# FPGA.net
KiCad netlist of a schematic drawn in Altium Designer
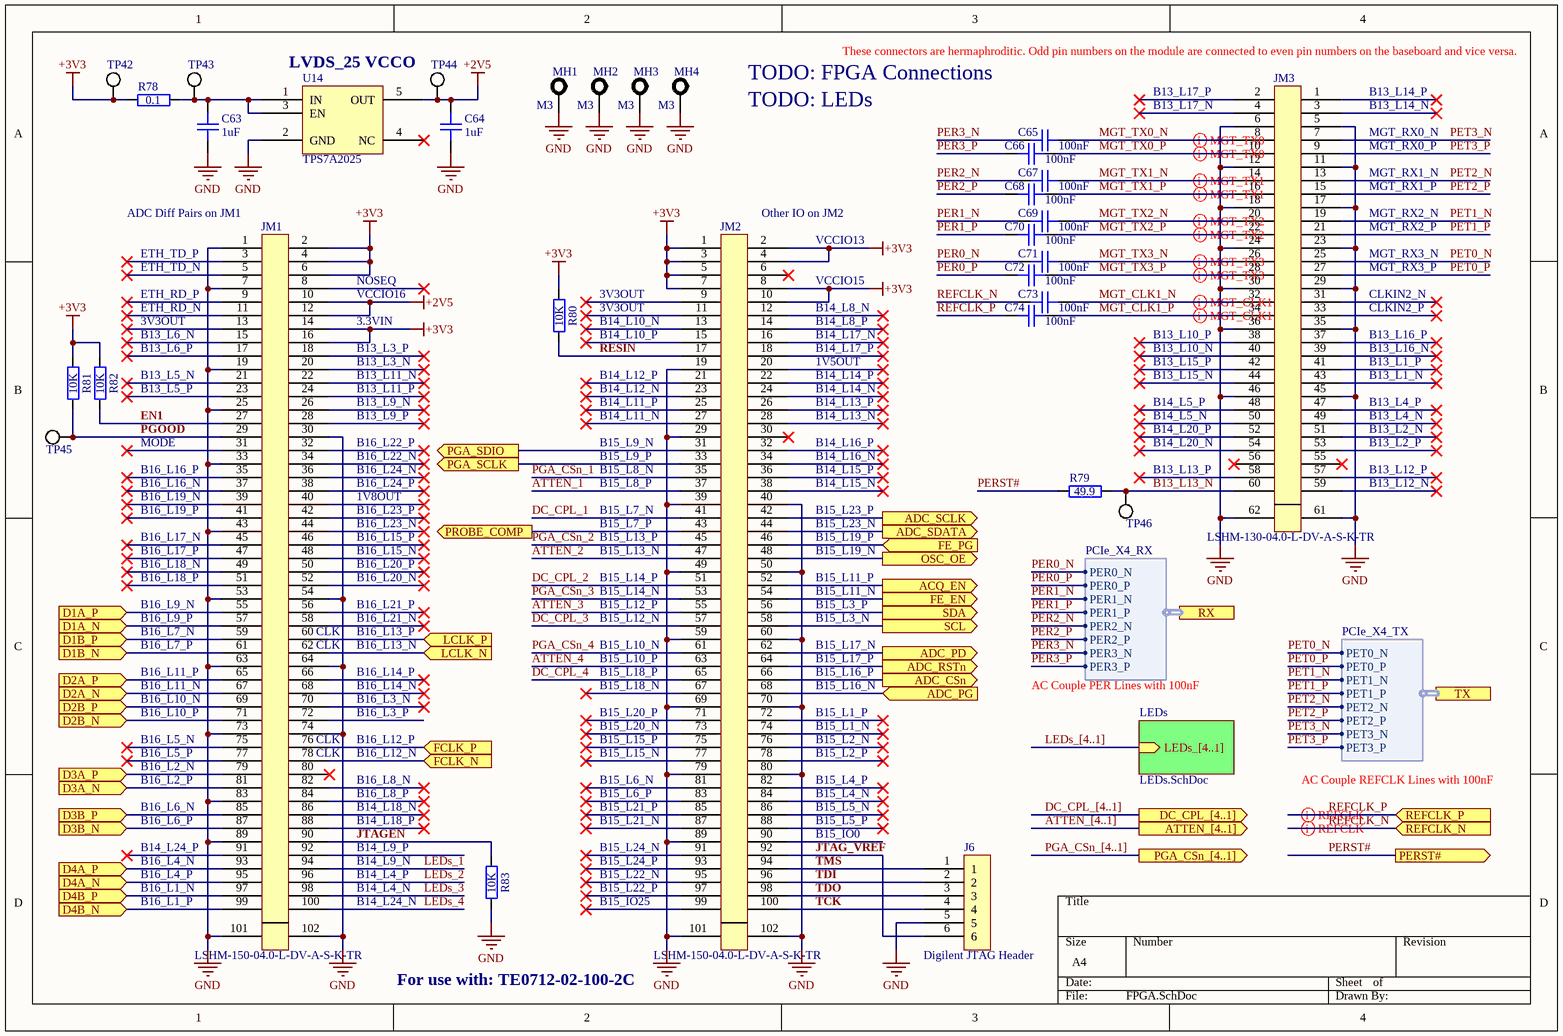
[diagram p0: FPGA.SchDoc]

(export (version "E")
  (design (tool "Eeschema 10.0.6"))
  (components
    (comp (ref "C63")
      (value "1uF")
      (footprint "GEN_C_0402")
      (libsource (lib "DSO") (part "CAP 1uF 25V X5R 0402"))
    )
    (comp (ref "C64")
      (value "1uF")
      (footprint "GEN_C_0402")
      (libsource (lib "DSO") (part "CAP 1uF 25V X5R 0402"))
    )
    (comp (ref "C65")
      (value "100nF")
      (footprint "GEN_C_0402")
      (libsource (lib "DSO") (part "CAP 100nF 16V X7R 0402"))
    )
    (comp (ref "C66")
      (value "100nF")
      (footprint "GEN_C_0402")
      (libsource (lib "DSO") (part "CAP 100nF 16V X7R 0402"))
    )
    (comp (ref "C67")
      (value "100nF")
      (footprint "GEN_C_0402")
      (libsource (lib "DSO") (part "CAP 100nF 16V X7R 0402"))
    )
    (comp (ref "C68")
      (value "100nF")
      (footprint "GEN_C_0402")
      (libsource (lib "DSO") (part "CAP 100nF 16V X7R 0402"))
    )
    (comp (ref "C69")
      (value "100nF")
      (footprint "GEN_C_0402")
      (libsource (lib "DSO") (part "CAP 100nF 16V X7R 0402"))
    )
    (comp (ref "C70")
      (value "100nF")
      (footprint "GEN_C_0402")
      (libsource (lib "DSO") (part "CAP 100nF 16V X7R 0402"))
    )
    (comp (ref "C71")
      (value "100nF")
      (footprint "GEN_C_0402")
      (libsource (lib "DSO") (part "CAP 100nF 16V X7R 0402"))
    )
    (comp (ref "C72")
      (value "100nF")
      (footprint "GEN_C_0402")
      (libsource (lib "DSO") (part "CAP 100nF 16V X7R 0402"))
    )
    (comp (ref "C73")
      (value "100nF")
      (footprint "GEN_C_0402")
      (libsource (lib "DSO") (part "CAP 100nF 16V X7R 0402"))
    )
    (comp (ref "C74")
      (value "100nF")
      (footprint "GEN_C_0402")
      (libsource (lib "DSO") (part "CAP 100nF 16V X7R 0402"))
    )
    (comp (ref "J6")
      (value "2.54mm 6 Pin TH")
      (footprint "GEN_2.54mm_6_Pin_TH_RA")
      (libsource (lib "DSO") (part "CONN 2.54mm 6 Pin TH RA"))
    )
    (comp (ref "JM1")
      (value "LSHM-150-04.0-L-DV-A-S-K-TR")
      (footprint "SAM_LSHM-150-XX.X-XX-DV-A-S")
      (libsource (lib "DSO") (part "CONN LSHM-150-04.0-L-DV-A-S-K-TR"))
    )
    (comp (ref "JM2")
      (value "LSHM-150-04.0-L-DV-A-S-K-TR")
      (footprint "SAM_LSHM-150-XX.X-XX-DV-A-S")
      (libsource (lib "DSO") (part "CONN LSHM-150-04.0-L-DV-A-S-K-TR"))
    )
    (comp (ref "JM3")
      (value "LSHM-130-04.0-L-DV-A-S-K-TR")
      (footprint "SAM_LSHM-130-XX.X-XX-DV-A-S")
      (libsource (lib "DSO") (part "CONN LSHM-130-04.0-L-DV-A-S-K-TR"))
    )
    (comp (ref "MH1") (value "M3") (footprint "MH M3") (libsource (lib "DSO") (part "MH M3")))
    (comp (ref "MH2") (value "M3") (footprint "MH M3") (libsource (lib "DSO") (part "MH M3")))
    (comp (ref "MH3") (value "M3") (footprint "MH M3") (libsource (lib "DSO") (part "MH M3")))
    (comp (ref "MH4") (value "M3") (footprint "MH M3") (libsource (lib "DSO") (part "MH M3")))
    (comp (ref "R78")
      (value "0.1")
      (footprint "GEN_R_0402")
      (fields (field (name "TOLERANCE") "1%"))
      (libsource (lib "DSO") (part "RES 0.1 OHM 1% 1/6W 0402"))
    )
    (comp (ref "R79")
      (value "49.9")
      (footprint "GEN_R_0402")
      (fields (field (name "TOLERANCE") "1%"))
      (libsource (lib "DSO") (part "RES 49.9 OHM 1% 1/10W 0402"))
    )
    (comp (ref "R80")
      (value "10K")
      (footprint "GEN_R_0402")
      (fields (field (name "TOLERANCE") "1%"))
      (libsource (lib "DSO") (part "RES 10K OHM 1% 1/10W 0402"))
    )
    (comp (ref "R81")
      (value "10K")
      (footprint "GEN_R_0402")
      (fields (field (name "TOLERANCE") "1%"))
      (libsource (lib "DSO") (part "RES 10K OHM 1% 1/10W 0402"))
    )
    (comp (ref "R82")
      (value "10K")
      (footprint "GEN_R_0402")
      (fields (field (name "TOLERANCE") "1%"))
      (libsource (lib "DSO") (part "RES 10K OHM 1% 1/10W 0402"))
    )
    (comp (ref "R83")
      (value "10K")
      (footprint "GEN_R_0402")
      (fields (field (name "TOLERANCE") "1%"))
      (libsource (lib "DSO") (part "RES 10K OHM 1% 1/10W 0402"))
    )
    (comp (ref "TP42") (value "PCB") (footprint "GEN_TP_PCB") (libsource (lib "DSO") (part "TP PCB 1mm")))
    (comp (ref "TP43") (value "PCB") (footprint "GEN_TP_PCB") (libsource (lib "DSO") (part "TP PCB 1mm")))
    (comp (ref "TP44") (value "PCB") (footprint "GEN_TP_PCB") (libsource (lib "DSO") (part "TP PCB 1mm")))
    (comp (ref "TP45") (value "PCB") (footprint "GEN_TP_PCB") (libsource (lib "DSO") (part "TP PCB 1mm")))
    (comp (ref "TP46") (value "PCB") (footprint "GEN_TP_PCB") (libsource (lib "DSO") (part "TP PCB 1mm")))
    (comp (ref "U14")
      (value "TPS7A2025")
      (footprint "GEN_SOT23_5_950_2900X1600X1450")
      (libsource (lib "DSO") (part "IC LDO TPS7A2025"))
    )
  )
  (nets
    (net (code "3") (name "+2V5") (class "Default")
      (node (ref "C64") (pin "2") (pinfunction "2_2") (pintype "passive"))
      (node (ref "JM1") (pin "10") (pinfunction "10_10") (pintype "passive"))
      (node (ref "JM1") (pin "12") (pinfunction "12_12") (pintype "passive"))
      (node (ref "TP44") (pin "1") (pinfunction "1_1") (pintype "passive"))
      (node (ref "U14") (pin "5") (pinfunction "OUT_5") (pintype "power_in"))
    )
    (net (code "4") (name "+3V3") (class "Default")
      (node (ref "JM1") (pin "14") (pinfunction "14_14") (pintype "passive"))
      (node (ref "JM1") (pin "16") (pinfunction "16_16") (pintype "passive"))
      (node (ref "JM1") (pin "2") (pinfunction "2_2") (pintype "passive"))
      (node (ref "JM1") (pin "4") (pinfunction "4_4") (pintype "passive"))
      (node (ref "JM1") (pin "6") (pinfunction "6_6") (pintype "passive"))
      (node (ref "JM2") (pin "1") (pinfunction "1_1") (pintype "passive"))
      (node (ref "JM2") (pin "10") (pinfunction "10_10") (pintype "passive"))
      (node (ref "JM2") (pin "2") (pinfunction "2_2") (pintype "passive"))
      (node (ref "JM2") (pin "3") (pinfunction "3_3") (pintype "passive"))
      (node (ref "JM2") (pin "4") (pinfunction "4_4") (pintype "passive"))
      (node (ref "JM2") (pin "5") (pinfunction "5_5") (pintype "passive"))
      (node (ref "JM2") (pin "7") (pinfunction "7_7") (pintype "passive"))
      (node (ref "JM2") (pin "8") (pinfunction "8_8") (pintype "passive"))
      (node (ref "R78") (pin "1") (pinfunction "1_1") (pintype "passive"))
      (node (ref "R80") (pin "2") (pinfunction "2_2") (pintype "passive"))
      (node (ref "R81") (pin "2") (pinfunction "2_2") (pintype "passive"))
      (node (ref "R82") (pin "2") (pinfunction "2_2") (pintype "passive"))
      (node (ref "TP42") (pin "1") (pinfunction "1_1") (pintype "passive"))
    )
    (net (code "5") (name "/ACQ_EN") (class "Default")
      (node (ref "JM2") (pin "52") (pinfunction "52_52") (pintype "passive"))
    )
    (net (code "6") (name "/ADC_CSn") (class "Default")
      (node (ref "JM2") (pin "66") (pinfunction "66_66") (pintype "passive"))
    )
    (net (code "7") (name "/ADC_PD") (class "Default")
      (node (ref "JM2") (pin "62") (pinfunction "62_62") (pintype "passive"))
    )
    (net (code "8") (name "/ADC_PG") (class "Default")
      (node (ref "JM2") (pin "68") (pinfunction "68_68") (pintype "passive"))
    )
    (net (code "9") (name "/ADC_RSTn") (class "Default")
      (node (ref "JM2") (pin "64") (pinfunction "64_64") (pintype "passive"))
    )
    (net (code "10") (name "/ADC_SCLK") (class "Default")
      (node (ref "JM2") (pin "42") (pinfunction "42_42") (pintype "passive"))
    )
    (net (code "11") (name "/ADC_SDATA") (class "Default")
      (node (ref "JM2") (pin "44") (pinfunction "44_44") (pintype "passive"))
    )
    (net (code "12") (name "/ATTEN_1") (class "Default")
      (node (ref "JM2") (pin "37") (pinfunction "37_37") (pintype "passive"))
    )
    (net (code "13") (name "/ATTEN_2") (class "Default")
      (node (ref "JM2") (pin "47") (pinfunction "47_47") (pintype "passive"))
    )
    (net (code "14") (name "/ATTEN_3") (class "Default")
      (node (ref "JM2") (pin "55") (pinfunction "55_55") (pintype "passive"))
    )
    (net (code "15") (name "/ATTEN_4") (class "Default")
      (node (ref "JM2") (pin "63") (pinfunction "63_63") (pintype "passive"))
    )
    (net (code "17") (name "/B13_L13_N") (class "Default")
      (node (ref "JM3") (pin "60") (pinfunction "60_60") (pintype "passive"))
      (node (ref "R79") (pin "2") (pinfunction "2_2") (pintype "passive"))
      (node (ref "TP46") (pin "1") (pinfunction "1_1") (pintype "passive"))
    )
    (net (code "18") (name "/D1A_N") (class "Default")
      (node (ref "JM1") (pin "57") (pinfunction "57_57") (pintype "passive"))
    )
    (net (code "19") (name "/D1A_P") (class "Default")
      (node (ref "JM1") (pin "55") (pinfunction "55_55") (pintype "passive"))
    )
    (net (code "20") (name "/D1B_N") (class "Default")
      (node (ref "JM1") (pin "61") (pinfunction "61_61") (pintype "passive"))
    )
    (net (code "21") (name "/D1B_P") (class "Default")
      (node (ref "JM1") (pin "59") (pinfunction "59_59") (pintype "passive"))
    )
    (net (code "22") (name "/D2A_N") (class "Default")
      (node (ref "JM1") (pin "67") (pinfunction "67_67") (pintype "passive"))
    )
    (net (code "23") (name "/D2A_P") (class "Default")
      (node (ref "JM1") (pin "65") (pinfunction "65_65") (pintype "passive"))
    )
    (net (code "24") (name "/D2B_N") (class "Default")
      (node (ref "JM1") (pin "71") (pinfunction "71_71") (pintype "passive"))
    )
    (net (code "25") (name "/D2B_P") (class "Default")
      (node (ref "JM1") (pin "69") (pinfunction "69_69") (pintype "passive"))
    )
    (net (code "26") (name "/D3A_N") (class "Default")
      (node (ref "JM1") (pin "81") (pinfunction "81_81") (pintype "passive"))
    )
    (net (code "27") (name "/D3A_P") (class "Default")
      (node (ref "JM1") (pin "79") (pinfunction "79_79") (pintype "passive"))
    )
    (net (code "28") (name "/D3B_N") (class "Default")
      (node (ref "JM1") (pin "87") (pinfunction "87_87") (pintype "passive"))
    )
    (net (code "29") (name "/D3B_P") (class "Default")
      (node (ref "JM1") (pin "85") (pinfunction "85_85") (pintype "passive"))
    )
    (net (code "30") (name "/D4A_N") (class "Default")
      (node (ref "JM1") (pin "95") (pinfunction "95_95") (pintype "passive"))
    )
    (net (code "31") (name "/D4A_P") (class "Default")
      (node (ref "JM1") (pin "93") (pinfunction "93_93") (pintype "passive"))
    )
    (net (code "32") (name "/D4B_N") (class "Default")
      (node (ref "JM1") (pin "99") (pinfunction "99_99") (pintype "passive"))
    )
    (net (code "33") (name "/D4B_P") (class "Default")
      (node (ref "JM1") (pin "97") (pinfunction "97_97") (pintype "passive"))
    )
    (net (code "34") (name "/DC_CPL_1") (class "Default")
      (node (ref "JM2") (pin "41") (pinfunction "41_41") (pintype "passive"))
    )
    (net (code "35") (name "/DC_CPL_2") (class "Default")
      (node (ref "JM2") (pin "51") (pinfunction "51_51") (pintype "passive"))
    )
    (net (code "36") (name "/DC_CPL_3") (class "Default")
      (node (ref "JM2") (pin "57") (pinfunction "57_57") (pintype "passive"))
    )
    (net (code "37") (name "/DC_CPL_4") (class "Default")
      (node (ref "JM2") (pin "65") (pinfunction "65_65") (pintype "passive"))
    )
    (net (code "39") (name "/EN1") (class "Default")
      (node (ref "JM1") (pin "27") (pinfunction "27_27") (pintype "passive"))
      (node (ref "R82") (pin "1") (pinfunction "1_1") (pintype "passive"))
    )
    (net (code "40") (name "/FCLK_N") (class "Default")
      (node (ref "JM1") (pin "78") (pinfunction "78_78") (pintype "passive"))
    )
    (net (code "41") (name "/FCLK_P") (class "Default")
      (node (ref "JM1") (pin "76") (pinfunction "76_76") (pintype "passive"))
    )
    (net (code "42") (name "/FE_EN") (class "Default")
      (node (ref "JM2") (pin "54") (pinfunction "54_54") (pintype "passive"))
    )
    (net (code "43") (name "/FE_PG") (class "Default")
      (node (ref "JM2") (pin "46") (pinfunction "46_46") (pintype "passive"))
    )
    (net (code "44") (name "/JTAGEN") (class "Default")
      (node (ref "JM1") (pin "90") (pinfunction "90_90") (pintype "passive"))
      (node (ref "R83") (pin "2") (pinfunction "2_2") (pintype "passive"))
    )
    (net (code "45") (name "/JTAG_VREF") (class "Default")
      (node (ref "J6") (pin "6") (pinfunction "6_6") (pintype "passive"))
      (node (ref "JM2") (pin "92") (pinfunction "92_92") (pintype "passive"))
    )
    (net (code "46") (name "/LCLK_N") (class "Default")
      (node (ref "JM1") (pin "62") (pinfunction "62_62") (pintype "passive"))
    )
    (net (code "47") (name "/LCLK_P") (class "Default")
      (node (ref "JM1") (pin "60") (pinfunction "60_60") (pintype "passive"))
    )
    (net (code "48") (name "/LEDs_1") (class "Default")
      (node (ref "JM1") (pin "94") (pinfunction "94_94") (pintype "passive"))
    )
    (net (code "49") (name "/LEDs_2") (class "Default")
      (node (ref "JM1") (pin "96") (pinfunction "96_96") (pintype "passive"))
    )
    (net (code "50") (name "/LEDs_3") (class "Default")
      (node (ref "JM1") (pin "98") (pinfunction "98_98") (pintype "passive"))
    )
    (net (code "51") (name "/LEDs_4") (class "Default")
      (node (ref "JM1") (pin "100") (pinfunction "100_100") (pintype "passive"))
    )
    (net (code "53") (name "/MGT_CLK1_N") (class "Default")
      (node (ref "C73") (pin "1") (pinfunction "1_1") (pintype "passive"))
      (node (ref "JM3") (pin "32") (pinfunction "32_32") (pintype "passive"))
    )
    (net (code "54") (name "/MGT_CLK1_P") (class "Default")
      (node (ref "C74") (pin "1") (pinfunction "1_1") (pintype "passive"))
      (node (ref "JM3") (pin "34") (pinfunction "34_34") (pintype "passive"))
    )
    (net (code "55") (name "/MGT_TX0_N") (class "Default")
      (node (ref "C65") (pin "1") (pinfunction "1_1") (pintype "passive"))
      (node (ref "JM3") (pin "8") (pinfunction "8_8") (pintype "passive"))
    )
    (net (code "56") (name "/MGT_TX0_P") (class "Default")
      (node (ref "C66") (pin "1") (pinfunction "1_1") (pintype "passive"))
      (node (ref "JM3") (pin "10") (pinfunction "10_10") (pintype "passive"))
    )
    (net (code "57") (name "/MGT_TX1_N") (class "Default")
      (node (ref "C67") (pin "1") (pinfunction "1_1") (pintype "passive"))
      (node (ref "JM3") (pin "14") (pinfunction "14_14") (pintype "passive"))
    )
    (net (code "58") (name "/MGT_TX1_P") (class "Default")
      (node (ref "C68") (pin "1") (pinfunction "1_1") (pintype "passive"))
      (node (ref "JM3") (pin "16") (pinfunction "16_16") (pintype "passive"))
    )
    (net (code "59") (name "/MGT_TX2_N") (class "Default")
      (node (ref "C69") (pin "1") (pinfunction "1_1") (pintype "passive"))
      (node (ref "JM3") (pin "20") (pinfunction "20_20") (pintype "passive"))
    )
    (net (code "60") (name "/MGT_TX2_P") (class "Default")
      (node (ref "C70") (pin "1") (pinfunction "1_1") (pintype "passive"))
      (node (ref "JM3") (pin "22") (pinfunction "22_22") (pintype "passive"))
    )
    (net (code "61") (name "/MGT_TX3_N") (class "Default")
      (node (ref "C71") (pin "1") (pinfunction "1_1") (pintype "passive"))
      (node (ref "JM3") (pin "26") (pinfunction "26_26") (pintype "passive"))
    )
    (net (code "62") (name "/MGT_TX3_P") (class "Default")
      (node (ref "C72") (pin "1") (pinfunction "1_1") (pintype "passive"))
      (node (ref "JM3") (pin "28") (pinfunction "28_28") (pintype "passive"))
    )
    (net (code "63") (name "/OSC_OE") (class "Default")
      (node (ref "JM2") (pin "48") (pinfunction "48_48") (pintype "passive"))
    )
    (net (code "64") (name "/PER0_N") (class "Default")
      (node (ref "C71") (pin "2") (pinfunction "2_2") (pintype "passive"))
    )
    (net (code "65") (name "/PER0_P") (class "Default")
      (node (ref "C72") (pin "2") (pinfunction "2_2") (pintype "passive"))
    )
    (net (code "66") (name "/PER1_N") (class "Default")
      (node (ref "C69") (pin "2") (pinfunction "2_2") (pintype "passive"))
    )
    (net (code "67") (name "/PER1_P") (class "Default")
      (node (ref "C70") (pin "2") (pinfunction "2_2") (pintype "passive"))
    )
    (net (code "68") (name "/PER2_N") (class "Default")
      (node (ref "C67") (pin "2") (pinfunction "2_2") (pintype "passive"))
    )
    (net (code "69") (name "/PER2_P") (class "Default")
      (node (ref "C68") (pin "2") (pinfunction "2_2") (pintype "passive"))
    )
    (net (code "70") (name "/PER3_N") (class "Default")
      (node (ref "C65") (pin "2") (pinfunction "2_2") (pintype "passive"))
    )
    (net (code "71") (name "/PER3_P") (class "Default")
      (node (ref "C66") (pin "2") (pinfunction "2_2") (pintype "passive"))
    )
    (net (code "72") (name "/PERST#") (class "Default")
      (node (ref "R79") (pin "1") (pinfunction "1_1") (pintype "passive"))
    )
    (net (code "73") (name "/PET0_N") (class "Default")
      (node (ref "JM3") (pin "25") (pinfunction "25_25") (pintype "passive"))
    )
    (net (code "74") (name "/PET0_P") (class "Default")
      (node (ref "JM3") (pin "27") (pinfunction "27_27") (pintype "passive"))
    )
    (net (code "75") (name "/PET1_N") (class "Default")
      (node (ref "JM3") (pin "19") (pinfunction "19_19") (pintype "passive"))
    )
    (net (code "76") (name "/PET1_P") (class "Default")
      (node (ref "JM3") (pin "21") (pinfunction "21_21") (pintype "passive"))
    )
    (net (code "77") (name "/PET2_N") (class "Default")
      (node (ref "JM3") (pin "13") (pinfunction "13_13") (pintype "passive"))
    )
    (net (code "78") (name "/PET2_P") (class "Default")
      (node (ref "JM3") (pin "15") (pinfunction "15_15") (pintype "passive"))
    )
    (net (code "79") (name "/PET3_N") (class "Default")
      (node (ref "JM3") (pin "7") (pinfunction "7_7") (pintype "passive"))
    )
    (net (code "80") (name "/PET3_P") (class "Default")
      (node (ref "JM3") (pin "9") (pinfunction "9_9") (pintype "passive"))
    )
    (net (code "81") (name "/PGA_CSn_1") (class "Default")
      (node (ref "JM2") (pin "35") (pinfunction "35_35") (pintype "passive"))
    )
    (net (code "82") (name "/PGA_CSn_2") (class "Default")
      (node (ref "JM2") (pin "45") (pinfunction "45_45") (pintype "passive"))
    )
    (net (code "83") (name "/PGA_CSn_3") (class "Default")
      (node (ref "JM2") (pin "53") (pinfunction "53_53") (pintype "passive"))
    )
    (net (code "84") (name "/PGA_CSn_4") (class "Default")
      (node (ref "JM2") (pin "61") (pinfunction "61_61") (pintype "passive"))
    )
    (net (code "86") (name "/PGA_SCLK") (class "Default")
      (node (ref "JM2") (pin "33") (pinfunction "33_33") (pintype "passive"))
    )
    (net (code "87") (name "/PGA_SDIO") (class "Default")
      (node (ref "JM2") (pin "31") (pinfunction "31_31") (pintype "passive"))
    )
    (net (code "88") (name "/PGOOD") (class "Default")
      (node (ref "JM1") (pin "29") (pinfunction "29_29") (pintype "passive"))
      (node (ref "R81") (pin "1") (pinfunction "1_1") (pintype "passive"))
      (node (ref "TP45") (pin "1") (pinfunction "1_1") (pintype "passive"))
    )
    (net (code "89") (name "/PROBE_COMP") (class "Default")
      (node (ref "JM2") (pin "43") (pinfunction "43_43") (pintype "passive"))
    )
    (net (code "90") (name "/REFCLK_N") (class "Default")
      (node (ref "C73") (pin "2") (pinfunction "2_2") (pintype "passive"))
    )
    (net (code "91") (name "/REFCLK_P") (class "Default")
      (node (ref "C74") (pin "2") (pinfunction "2_2") (pintype "passive"))
    )
    (net (code "92") (name "/RESIN") (class "Default")
      (node (ref "JM2") (pin "17") (pinfunction "17_17") (pintype "passive"))
      (node (ref "R80") (pin "1") (pinfunction "1_1") (pintype "passive"))
    )
    (net (code "93") (name "/SCL") (class "Default")
      (node (ref "JM2") (pin "58") (pinfunction "58_58") (pintype "passive"))
    )
    (net (code "94") (name "/SDA") (class "Default")
      (node (ref "JM2") (pin "56") (pinfunction "56_56") (pintype "passive"))
    )
    (net (code "95") (name "/TCK") (class "Default")
      (node (ref "J6") (pin "4") (pinfunction "4_4") (pintype "passive"))
      (node (ref "JM2") (pin "100") (pinfunction "100_100") (pintype "passive"))
    )
    (net (code "96") (name "/TDI") (class "Default")
      (node (ref "J6") (pin "2") (pinfunction "2_2") (pintype "passive"))
      (node (ref "JM2") (pin "96") (pinfunction "96_96") (pintype "passive"))
    )
    (net (code "97") (name "/TDO") (class "Default")
      (node (ref "J6") (pin "3") (pinfunction "3_3") (pintype "passive"))
      (node (ref "JM2") (pin "98") (pinfunction "98_98") (pintype "passive"))
    )
    (net (code "98") (name "/TMS") (class "Default")
      (node (ref "J6") (pin "1") (pinfunction "1_1") (pintype "passive"))
      (node (ref "JM2") (pin "94") (pinfunction "94_94") (pintype "passive"))
    )
    (net (code "101") (name "GND") (class "Default")
      (node (ref "C63") (pin "1") (pinfunction "1_1") (pintype "passive"))
      (node (ref "C64") (pin "1") (pinfunction "1_1") (pintype "passive"))
      (node (ref "J6") (pin "5") (pinfunction "5_5") (pintype "passive"))
      (node (ref "JM1") (pin "1") (pinfunction "1_1") (pintype "passive"))
      (node (ref "JM1") (pin "101") (pinfunction "101_101") (pintype "passive"))
      (node (ref "JM1") (pin "102") (pinfunction "102_102") (pintype "passive"))
      (node (ref "JM1") (pin "19") (pinfunction "19_19") (pintype "passive"))
      (node (ref "JM1") (pin "25") (pinfunction "25_25") (pintype "passive"))
      (node (ref "JM1") (pin "30") (pinfunction "30_30") (pintype "passive"))
      (node (ref "JM1") (pin "33") (pinfunction "33_33") (pintype "passive"))
      (node (ref "JM1") (pin "43") (pinfunction "43_43") (pintype "passive"))
      (node (ref "JM1") (pin "53") (pinfunction "53_53") (pintype "passive"))
      (node (ref "JM1") (pin "54") (pinfunction "54_54") (pintype "passive"))
      (node (ref "JM1") (pin "63") (pinfunction "63_63") (pintype "passive"))
      (node (ref "JM1") (pin "64") (pinfunction "64_64") (pintype "passive"))
      (node (ref "JM1") (pin "7") (pinfunction "7_7") (pintype "passive"))
      (node (ref "JM1") (pin "73") (pinfunction "73_73") (pintype "passive"))
      (node (ref "JM1") (pin "74") (pinfunction "74_74") (pintype "passive"))
      (node (ref "JM1") (pin "83") (pinfunction "83_83") (pintype "passive"))
      (node (ref "JM1") (pin "89") (pinfunction "89_89") (pintype "passive"))
      (node (ref "JM2") (pin "101") (pinfunction "101_101") (pintype "passive"))
      (node (ref "JM2") (pin "102") (pinfunction "102_102") (pintype "passive"))
      (node (ref "JM2") (pin "19") (pinfunction "19_19") (pintype "passive"))
      (node (ref "JM2") (pin "29") (pinfunction "29_29") (pintype "passive"))
      (node (ref "JM2") (pin "39") (pinfunction "39_39") (pintype "passive"))
      (node (ref "JM2") (pin "40") (pinfunction "40_40") (pintype "passive"))
      (node (ref "JM2") (pin "49") (pinfunction "49_49") (pintype "passive"))
      (node (ref "JM2") (pin "50") (pinfunction "50_50") (pintype "passive"))
      (node (ref "JM2") (pin "59") (pinfunction "59_59") (pintype "passive"))
      (node (ref "JM2") (pin "60") (pinfunction "60_60") (pintype "passive"))
      (node (ref "JM2") (pin "69") (pinfunction "69_69") (pintype "passive"))
      (node (ref "JM2") (pin "70") (pinfunction "70_70") (pintype "passive"))
      (node (ref "JM2") (pin "79") (pinfunction "79_79") (pintype "passive"))
      (node (ref "JM2") (pin "80") (pinfunction "80_80") (pintype "passive"))
      (node (ref "JM2") (pin "89") (pinfunction "89_89") (pintype "passive"))
      (node (ref "JM3") (pin "11") (pinfunction "11_11") (pintype "passive"))
      (node (ref "JM3") (pin "12") (pinfunction "12_12") (pintype "passive"))
      (node (ref "JM3") (pin "17") (pinfunction "17_17") (pintype "passive"))
      (node (ref "JM3") (pin "18") (pinfunction "18_18") (pintype "passive"))
      (node (ref "JM3") (pin "23") (pinfunction "23_23") (pintype "passive"))
      (node (ref "JM3") (pin "24") (pinfunction "24_24") (pintype "passive"))
      (node (ref "JM3") (pin "29") (pinfunction "29_29") (pintype "passive"))
      (node (ref "JM3") (pin "30") (pinfunction "30_30") (pintype "passive"))
      (node (ref "JM3") (pin "35") (pinfunction "35_35") (pintype "passive"))
      (node (ref "JM3") (pin "36") (pinfunction "36_36") (pintype "passive"))
      (node (ref "JM3") (pin "45") (pinfunction "45_45") (pintype "passive"))
      (node (ref "JM3") (pin "46") (pinfunction "46_46") (pintype "passive"))
      (node (ref "JM3") (pin "5") (pinfunction "5_5") (pintype "passive"))
      (node (ref "JM3") (pin "6") (pinfunction "6_6") (pintype "passive"))
      (node (ref "JM3") (pin "61") (pinfunction "61_61") (pintype "passive"))
      (node (ref "JM3") (pin "62") (pinfunction "62_62") (pintype "passive"))
      (node (ref "MH1") (pin "1") (pinfunction "1_1") (pintype "passive"))
      (node (ref "MH2") (pin "1") (pinfunction "1_1") (pintype "passive"))
      (node (ref "MH3") (pin "1") (pinfunction "1_1") (pintype "passive"))
      (node (ref "MH4") (pin "1") (pinfunction "1_1") (pintype "passive"))
      (node (ref "R83") (pin "1") (pinfunction "1_1") (pintype "passive"))
      (node (ref "U14") (pin "2") (pinfunction "GND_2") (pintype "power_in"))
    )
    (net (code "102") (name "Net-(U14-EN)") (class "Default")
      (node (ref "C63") (pin "2") (pinfunction "2_2") (pintype "passive"))
      (node (ref "R78") (pin "2") (pinfunction "2_2") (pintype "passive"))
      (node (ref "TP43") (pin "1") (pinfunction "1_1") (pintype "passive"))
      (node (ref "U14") (pin "1") (pinfunction "IN_1") (pintype "power_in"))
      (node (ref "U14") (pin "3") (pinfunction "EN_3") (pintype "passive"))
    )
    (net (code "103") (name "unconnected-(JM1-Pad3)") (class "Default")
      (node (ref "JM1") (pin "3") (pinfunction "3_3") (pintype "passive+no_connect"))
    )
    (net (code "104") (name "unconnected-(JM1-Pad5)") (class "Default")
      (node (ref "JM1") (pin "5") (pinfunction "5_5") (pintype "passive+no_connect"))
    )
    (net (code "105") (name "unconnected-(JM1-Pad8)") (class "Default")
      (node (ref "JM1") (pin "8") (pinfunction "8_8") (pintype "passive+no_connect"))
    )
    (net (code "106") (name "unconnected-(JM1-Pad9)") (class "Default")
      (node (ref "JM1") (pin "9") (pinfunction "9_9") (pintype "passive+no_connect"))
    )
    (net (code "107") (name "unconnected-(JM1-Pad11)") (class "Default")
      (node (ref "JM1") (pin "11") (pinfunction "11_11") (pintype "passive+no_connect"))
    )
    (net (code "108") (name "unconnected-(JM1-Pad13)") (class "Default")
      (node (ref "JM1") (pin "13") (pinfunction "13_13") (pintype "passive+no_connect"))
    )
    (net (code "109") (name "unconnected-(JM1-Pad15)") (class "Default")
      (node (ref "JM1") (pin "15") (pinfunction "15_15") (pintype "passive+no_connect"))
    )
    (net (code "110") (name "unconnected-(JM1-Pad17)") (class "Default")
      (node (ref "JM1") (pin "17") (pinfunction "17_17") (pintype "passive+no_connect"))
    )
    (net (code "111") (name "unconnected-(JM1-Pad18)") (class "Default")
      (node (ref "JM1") (pin "18") (pinfunction "18_18") (pintype "passive+no_connect"))
    )
    (net (code "112") (name "unconnected-(JM1-Pad20)") (class "Default")
      (node (ref "JM1") (pin "20") (pinfunction "20_20") (pintype "passive+no_connect"))
    )
    (net (code "113") (name "unconnected-(JM1-Pad21)") (class "Default")
      (node (ref "JM1") (pin "21") (pinfunction "21_21") (pintype "passive+no_connect"))
    )
    (net (code "114") (name "unconnected-(JM1-Pad22)") (class "Default")
      (node (ref "JM1") (pin "22") (pinfunction "22_22") (pintype "passive+no_connect"))
    )
    (net (code "115") (name "unconnected-(JM1-Pad23)") (class "Default")
      (node (ref "JM1") (pin "23") (pinfunction "23_23") (pintype "passive+no_connect"))
    )
    (net (code "116") (name "unconnected-(JM1-Pad24)") (class "Default")
      (node (ref "JM1") (pin "24") (pinfunction "24_24") (pintype "passive+no_connect"))
    )
    (net (code "117") (name "unconnected-(JM1-Pad26)") (class "Default")
      (node (ref "JM1") (pin "26") (pinfunction "26_26") (pintype "passive+no_connect"))
    )
    (net (code "118") (name "unconnected-(JM1-Pad28)") (class "Default")
      (node (ref "JM1") (pin "28") (pinfunction "28_28") (pintype "passive+no_connect"))
    )
    (net (code "119") (name "unconnected-(JM1-Pad31)") (class "Default")
      (node (ref "JM1") (pin "31") (pinfunction "31_31") (pintype "passive+no_connect"))
    )
    (net (code "120") (name "unconnected-(JM1-Pad32)") (class "Default")
      (node (ref "JM1") (pin "32") (pinfunction "32_32") (pintype "passive+no_connect"))
    )
    (net (code "121") (name "unconnected-(JM1-Pad34)") (class "Default")
      (node (ref "JM1") (pin "34") (pinfunction "34_34") (pintype "passive+no_connect"))
    )
    (net (code "122") (name "unconnected-(JM1-Pad35)") (class "Default")
      (node (ref "JM1") (pin "35") (pinfunction "35_35") (pintype "passive+no_connect"))
    )
    (net (code "123") (name "unconnected-(JM1-Pad36)") (class "Default")
      (node (ref "JM1") (pin "36") (pinfunction "36_36") (pintype "passive+no_connect"))
    )
    (net (code "124") (name "unconnected-(JM1-Pad37)") (class "Default")
      (node (ref "JM1") (pin "37") (pinfunction "37_37") (pintype "passive+no_connect"))
    )
    (net (code "125") (name "unconnected-(JM1-Pad38)") (class "Default")
      (node (ref "JM1") (pin "38") (pinfunction "38_38") (pintype "passive+no_connect"))
    )
    (net (code "126") (name "unconnected-(JM1-Pad39)") (class "Default")
      (node (ref "JM1") (pin "39") (pinfunction "39_39") (pintype "passive+no_connect"))
    )
    (net (code "127") (name "unconnected-(JM1-Pad40)") (class "Default")
      (node (ref "JM1") (pin "40") (pinfunction "40_40") (pintype "passive+no_connect"))
    )
    (net (code "128") (name "unconnected-(JM1-Pad41)") (class "Default")
      (node (ref "JM1") (pin "41") (pinfunction "41_41") (pintype "passive+no_connect"))
    )
    (net (code "129") (name "unconnected-(JM1-Pad42)") (class "Default")
      (node (ref "JM1") (pin "42") (pinfunction "42_42") (pintype "passive+no_connect"))
    )
    (net (code "130") (name "unconnected-(JM1-Pad44)") (class "Default")
      (node (ref "JM1") (pin "44") (pinfunction "44_44") (pintype "passive+no_connect"))
    )
    (net (code "131") (name "unconnected-(JM1-Pad45)") (class "Default")
      (node (ref "JM1") (pin "45") (pinfunction "45_45") (pintype "passive+no_connect"))
    )
    (net (code "132") (name "unconnected-(JM1-Pad46)") (class "Default")
      (node (ref "JM1") (pin "46") (pinfunction "46_46") (pintype "passive+no_connect"))
    )
    (net (code "133") (name "unconnected-(JM1-Pad47)") (class "Default")
      (node (ref "JM1") (pin "47") (pinfunction "47_47") (pintype "passive+no_connect"))
    )
    (net (code "134") (name "unconnected-(JM1-Pad48)") (class "Default")
      (node (ref "JM1") (pin "48") (pinfunction "48_48") (pintype "passive+no_connect"))
    )
    (net (code "135") (name "unconnected-(JM1-Pad49)") (class "Default")
      (node (ref "JM1") (pin "49") (pinfunction "49_49") (pintype "passive+no_connect"))
    )
    (net (code "136") (name "unconnected-(JM1-Pad50)") (class "Default")
      (node (ref "JM1") (pin "50") (pinfunction "50_50") (pintype "passive+no_connect"))
    )
    (net (code "137") (name "unconnected-(JM1-Pad51)") (class "Default")
      (node (ref "JM1") (pin "51") (pinfunction "51_51") (pintype "passive+no_connect"))
    )
    (net (code "138") (name "unconnected-(JM1-Pad52)") (class "Default")
      (node (ref "JM1") (pin "52") (pinfunction "52_52") (pintype "passive+no_connect"))
    )
    (net (code "139") (name "unconnected-(JM1-Pad56)") (class "Default")
      (node (ref "JM1") (pin "56") (pinfunction "56_56") (pintype "passive+no_connect"))
    )
    (net (code "140") (name "unconnected-(JM1-Pad58)") (class "Default")
      (node (ref "JM1") (pin "58") (pinfunction "58_58") (pintype "passive+no_connect"))
    )
    (net (code "141") (name "unconnected-(JM1-Pad66)") (class "Default")
      (node (ref "JM1") (pin "66") (pinfunction "66_66") (pintype "passive+no_connect"))
    )
    (net (code "142") (name "unconnected-(JM1-Pad68)") (class "Default")
      (node (ref "JM1") (pin "68") (pinfunction "68_68") (pintype "passive+no_connect"))
    )
    (net (code "143") (name "unconnected-(JM1-Pad70)") (class "Default")
      (node (ref "JM1") (pin "70") (pinfunction "70_70") (pintype "passive+no_connect"))
    )
    (net (code "144") (name "unconnected-(JM1-Pad72)") (class "Default")
      (node (ref "JM1") (pin "72") (pinfunction "72_72") (pintype "passive"))
    )
    (net (code "145") (name "unconnected-(JM1-Pad75)") (class "Default")
      (node (ref "JM1") (pin "75") (pinfunction "75_75") (pintype "passive+no_connect"))
    )
    (net (code "146") (name "unconnected-(JM1-Pad77)") (class "Default")
      (node (ref "JM1") (pin "77") (pinfunction "77_77") (pintype "passive+no_connect"))
    )
    (net (code "147") (name "unconnected-(JM1-Pad80)") (class "Default")
      (node (ref "JM1") (pin "80") (pinfunction "80_80") (pintype "passive+no_connect"))
    )
    (net (code "148") (name "unconnected-(JM1-Pad82)") (class "Default")
      (node (ref "JM1") (pin "82") (pinfunction "82_82") (pintype "passive+no_connect"))
    )
    (net (code "149") (name "unconnected-(JM1-Pad84)") (class "Default")
      (node (ref "JM1") (pin "84") (pinfunction "84_84") (pintype "passive+no_connect"))
    )
    (net (code "150") (name "unconnected-(JM1-Pad86)") (class "Default")
      (node (ref "JM1") (pin "86") (pinfunction "86_86") (pintype "passive+no_connect"))
    )
    (net (code "151") (name "unconnected-(JM1-Pad88)") (class "Default")
      (node (ref "JM1") (pin "88") (pinfunction "88_88") (pintype "passive+no_connect"))
    )
    (net (code "152") (name "unconnected-(JM1-Pad91)") (class "Default")
      (node (ref "JM1") (pin "91") (pinfunction "91_91") (pintype "passive+no_connect"))
    )
    (net (code "153") (name "unconnected-(JM1-Pad92)") (class "Default")
      (node (ref "JM1") (pin "92") (pinfunction "92_92") (pintype "passive"))
    )
    (net (code "154") (name "unconnected-(JM2-Pad6)") (class "Default")
      (node (ref "JM2") (pin "6") (pinfunction "6_6") (pintype "passive+no_connect"))
    )
    (net (code "155") (name "unconnected-(JM2-Pad9)") (class "Default")
      (node (ref "JM2") (pin "9") (pinfunction "9_9") (pintype "passive+no_connect"))
    )
    (net (code "156") (name "unconnected-(JM2-Pad11)") (class "Default")
      (node (ref "JM2") (pin "11") (pinfunction "11_11") (pintype "passive+no_connect"))
    )
    (net (code "157") (name "unconnected-(JM2-Pad12)") (class "Default")
      (node (ref "JM2") (pin "12") (pinfunction "12_12") (pintype "passive+no_connect"))
    )
    (net (code "158") (name "unconnected-(JM2-Pad13)") (class "Default")
      (node (ref "JM2") (pin "13") (pinfunction "13_13") (pintype "passive+no_connect"))
    )
    (net (code "159") (name "unconnected-(JM2-Pad14)") (class "Default")
      (node (ref "JM2") (pin "14") (pinfunction "14_14") (pintype "passive+no_connect"))
    )
    (net (code "160") (name "unconnected-(JM2-Pad15)") (class "Default")
      (node (ref "JM2") (pin "15") (pinfunction "15_15") (pintype "passive+no_connect"))
    )
    (net (code "161") (name "unconnected-(JM2-Pad16)") (class "Default")
      (node (ref "JM2") (pin "16") (pinfunction "16_16") (pintype "passive+no_connect"))
    )
    (net (code "162") (name "unconnected-(JM2-Pad18)") (class "Default")
      (node (ref "JM2") (pin "18") (pinfunction "18_18") (pintype "passive+no_connect"))
    )
    (net (code "163") (name "unconnected-(JM2-Pad20)") (class "Default")
      (node (ref "JM2") (pin "20") (pinfunction "20_20") (pintype "passive+no_connect"))
    )
    (net (code "164") (name "unconnected-(JM2-Pad21)") (class "Default")
      (node (ref "JM2") (pin "21") (pinfunction "21_21") (pintype "passive+no_connect"))
    )
    (net (code "165") (name "unconnected-(JM2-Pad22)") (class "Default")
      (node (ref "JM2") (pin "22") (pinfunction "22_22") (pintype "passive+no_connect"))
    )
    (net (code "166") (name "unconnected-(JM2-Pad23)") (class "Default")
      (node (ref "JM2") (pin "23") (pinfunction "23_23") (pintype "passive+no_connect"))
    )
    (net (code "167") (name "unconnected-(JM2-Pad24)") (class "Default")
      (node (ref "JM2") (pin "24") (pinfunction "24_24") (pintype "passive+no_connect"))
    )
    (net (code "168") (name "unconnected-(JM2-Pad25)") (class "Default")
      (node (ref "JM2") (pin "25") (pinfunction "25_25") (pintype "passive+no_connect"))
    )
    (net (code "169") (name "unconnected-(JM2-Pad26)") (class "Default")
      (node (ref "JM2") (pin "26") (pinfunction "26_26") (pintype "passive+no_connect"))
    )
    (net (code "170") (name "unconnected-(JM2-Pad27)") (class "Default")
      (node (ref "JM2") (pin "27") (pinfunction "27_27") (pintype "passive+no_connect"))
    )
    (net (code "171") (name "unconnected-(JM2-Pad28)") (class "Default")
      (node (ref "JM2") (pin "28") (pinfunction "28_28") (pintype "passive+no_connect"))
    )
    (net (code "172") (name "unconnected-(JM2-Pad30)") (class "Default")
      (node (ref "JM2") (pin "30") (pinfunction "30_30") (pintype "passive+no_connect"))
    )
    (net (code "173") (name "unconnected-(JM2-Pad32)") (class "Default")
      (node (ref "JM2") (pin "32") (pinfunction "32_32") (pintype "passive+no_connect"))
    )
    (net (code "174") (name "unconnected-(JM2-Pad34)") (class "Default")
      (node (ref "JM2") (pin "34") (pinfunction "34_34") (pintype "passive+no_connect"))
    )
    (net (code "175") (name "unconnected-(JM2-Pad36)") (class "Default")
      (node (ref "JM2") (pin "36") (pinfunction "36_36") (pintype "passive+no_connect"))
    )
    (net (code "176") (name "unconnected-(JM2-Pad38)") (class "Default")
      (node (ref "JM2") (pin "38") (pinfunction "38_38") (pintype "passive+no_connect"))
    )
    (net (code "177") (name "unconnected-(JM2-Pad67)") (class "Default")
      (node (ref "JM2") (pin "67") (pinfunction "67_67") (pintype "passive+no_connect"))
    )
    (net (code "178") (name "unconnected-(JM2-Pad71)") (class "Default")
      (node (ref "JM2") (pin "71") (pinfunction "71_71") (pintype "passive+no_connect"))
    )
    (net (code "179") (name "unconnected-(JM2-Pad72)") (class "Default")
      (node (ref "JM2") (pin "72") (pinfunction "72_72") (pintype "passive+no_connect"))
    )
    (net (code "180") (name "unconnected-(JM2-Pad73)") (class "Default")
      (node (ref "JM2") (pin "73") (pinfunction "73_73") (pintype "passive+no_connect"))
    )
    (net (code "181") (name "unconnected-(JM2-Pad74)") (class "Default")
      (node (ref "JM2") (pin "74") (pinfunction "74_74") (pintype "passive+no_connect"))
    )
    (net (code "182") (name "unconnected-(JM2-Pad75)") (class "Default")
      (node (ref "JM2") (pin "75") (pinfunction "75_75") (pintype "passive+no_connect"))
    )
    (net (code "183") (name "unconnected-(JM2-Pad76)") (class "Default")
      (node (ref "JM2") (pin "76") (pinfunction "76_76") (pintype "passive+no_connect"))
    )
    (net (code "184") (name "unconnected-(JM2-Pad77)") (class "Default")
      (node (ref "JM2") (pin "77") (pinfunction "77_77") (pintype "passive+no_connect"))
    )
    (net (code "185") (name "unconnected-(JM2-Pad78)") (class "Default")
      (node (ref "JM2") (pin "78") (pinfunction "78_78") (pintype "passive+no_connect"))
    )
    (net (code "186") (name "unconnected-(JM2-Pad81)") (class "Default")
      (node (ref "JM2") (pin "81") (pinfunction "81_81") (pintype "passive+no_connect"))
    )
    (net (code "187") (name "unconnected-(JM2-Pad82)") (class "Default")
      (node (ref "JM2") (pin "82") (pinfunction "82_82") (pintype "passive+no_connect"))
    )
    (net (code "188") (name "unconnected-(JM2-Pad83)") (class "Default")
      (node (ref "JM2") (pin "83") (pinfunction "83_83") (pintype "passive+no_connect"))
    )
    (net (code "189") (name "unconnected-(JM2-Pad84)") (class "Default")
      (node (ref "JM2") (pin "84") (pinfunction "84_84") (pintype "passive+no_connect"))
    )
    (net (code "190") (name "unconnected-(JM2-Pad85)") (class "Default")
      (node (ref "JM2") (pin "85") (pinfunction "85_85") (pintype "passive+no_connect"))
    )
    (net (code "191") (name "unconnected-(JM2-Pad86)") (class "Default")
      (node (ref "JM2") (pin "86") (pinfunction "86_86") (pintype "passive+no_connect"))
    )
    (net (code "192") (name "unconnected-(JM2-Pad87)") (class "Default")
      (node (ref "JM2") (pin "87") (pinfunction "87_87") (pintype "passive+no_connect"))
    )
    (net (code "193") (name "unconnected-(JM2-Pad88)") (class "Default")
      (node (ref "JM2") (pin "88") (pinfunction "88_88") (pintype "passive+no_connect"))
    )
    (net (code "194") (name "unconnected-(JM2-Pad90)") (class "Default")
      (node (ref "JM2") (pin "90") (pinfunction "90_90") (pintype "passive"))
    )
    (net (code "195") (name "unconnected-(JM2-Pad91)") (class "Default")
      (node (ref "JM2") (pin "91") (pinfunction "91_91") (pintype "passive+no_connect"))
    )
    (net (code "196") (name "unconnected-(JM2-Pad93)") (class "Default")
      (node (ref "JM2") (pin "93") (pinfunction "93_93") (pintype "passive+no_connect"))
    )
    (net (code "197") (name "unconnected-(JM2-Pad95)") (class "Default")
      (node (ref "JM2") (pin "95") (pinfunction "95_95") (pintype "passive+no_connect"))
    )
    (net (code "198") (name "unconnected-(JM2-Pad97)") (class "Default")
      (node (ref "JM2") (pin "97") (pinfunction "97_97") (pintype "passive+no_connect"))
    )
    (net (code "199") (name "unconnected-(JM2-Pad99)") (class "Default")
      (node (ref "JM2") (pin "99") (pinfunction "99_99") (pintype "passive+no_connect"))
    )
    (net (code "200") (name "unconnected-(JM3-Pad1)") (class "Default")
      (node (ref "JM3") (pin "1") (pinfunction "1_1") (pintype "passive+no_connect"))
    )
    (net (code "201") (name "unconnected-(JM3-Pad2)") (class "Default")
      (node (ref "JM3") (pin "2") (pinfunction "2_2") (pintype "passive+no_connect"))
    )
    (net (code "202") (name "unconnected-(JM3-Pad3)") (class "Default")
      (node (ref "JM3") (pin "3") (pinfunction "3_3") (pintype "passive+no_connect"))
    )
    (net (code "203") (name "unconnected-(JM3-Pad4)") (class "Default")
      (node (ref "JM3") (pin "4") (pinfunction "4_4") (pintype "passive+no_connect"))
    )
    (net (code "204") (name "unconnected-(JM3-Pad31)") (class "Default")
      (node (ref "JM3") (pin "31") (pinfunction "31_31") (pintype "passive+no_connect"))
    )
    (net (code "205") (name "unconnected-(JM3-Pad33)") (class "Default")
      (node (ref "JM3") (pin "33") (pinfunction "33_33") (pintype "passive+no_connect"))
    )
    (net (code "206") (name "unconnected-(JM3-Pad37)") (class "Default")
      (node (ref "JM3") (pin "37") (pinfunction "37_37") (pintype "passive+no_connect"))
    )
    (net (code "207") (name "unconnected-(JM3-Pad38)") (class "Default")
      (node (ref "JM3") (pin "38") (pinfunction "38_38") (pintype "passive+no_connect"))
    )
    (net (code "208") (name "unconnected-(JM3-Pad39)") (class "Default")
      (node (ref "JM3") (pin "39") (pinfunction "39_39") (pintype "passive+no_connect"))
    )
    (net (code "209") (name "unconnected-(JM3-Pad40)") (class "Default")
      (node (ref "JM3") (pin "40") (pinfunction "40_40") (pintype "passive+no_connect"))
    )
    (net (code "210") (name "unconnected-(JM3-Pad41)") (class "Default")
      (node (ref "JM3") (pin "41") (pinfunction "41_41") (pintype "passive+no_connect"))
    )
    (net (code "211") (name "unconnected-(JM3-Pad42)") (class "Default")
      (node (ref "JM3") (pin "42") (pinfunction "42_42") (pintype "passive+no_connect"))
    )
    (net (code "212") (name "unconnected-(JM3-Pad43)") (class "Default")
      (node (ref "JM3") (pin "43") (pinfunction "43_43") (pintype "passive+no_connect"))
    )
    (net (code "213") (name "unconnected-(JM3-Pad44)") (class "Default")
      (node (ref "JM3") (pin "44") (pinfunction "44_44") (pintype "passive+no_connect"))
    )
    (net (code "214") (name "unconnected-(JM3-Pad47)") (class "Default")
      (node (ref "JM3") (pin "47") (pinfunction "47_47") (pintype "passive+no_connect"))
    )
    (net (code "215") (name "unconnected-(JM3-Pad48)") (class "Default")
      (node (ref "JM3") (pin "48") (pinfunction "48_48") (pintype "passive+no_connect"))
    )
    (net (code "216") (name "unconnected-(JM3-Pad49)") (class "Default")
      (node (ref "JM3") (pin "49") (pinfunction "49_49") (pintype "passive+no_connect"))
    )
    (net (code "217") (name "unconnected-(JM3-Pad50)") (class "Default")
      (node (ref "JM3") (pin "50") (pinfunction "50_50") (pintype "passive+no_connect"))
    )
    (net (code "218") (name "unconnected-(JM3-Pad51)") (class "Default")
      (node (ref "JM3") (pin "51") (pinfunction "51_51") (pintype "passive+no_connect"))
    )
    (net (code "219") (name "unconnected-(JM3-Pad52)") (class "Default")
      (node (ref "JM3") (pin "52") (pinfunction "52_52") (pintype "passive+no_connect"))
    )
    (net (code "220") (name "unconnected-(JM3-Pad53)") (class "Default")
      (node (ref "JM3") (pin "53") (pinfunction "53_53") (pintype "passive+no_connect"))
    )
    (net (code "221") (name "unconnected-(JM3-Pad54)") (class "Default")
      (node (ref "JM3") (pin "54") (pinfunction "54_54") (pintype "passive+no_connect"))
    )
    (net (code "222") (name "unconnected-(JM3-Pad55)") (class "Default")
      (node (ref "JM3") (pin "55") (pinfunction "55_55") (pintype "passive+no_connect"))
    )
    (net (code "223") (name "unconnected-(JM3-Pad56)") (class "Default")
      (node (ref "JM3") (pin "56") (pinfunction "56_56") (pintype "passive+no_connect"))
    )
    (net (code "224") (name "unconnected-(JM3-Pad57)") (class "Default")
      (node (ref "JM3") (pin "57") (pinfunction "57_57") (pintype "passive+no_connect"))
    )
    (net (code "225") (name "unconnected-(JM3-Pad58)") (class "Default")
      (node (ref "JM3") (pin "58") (pinfunction "58_58") (pintype "passive+no_connect"))
    )
    (net (code "226") (name "unconnected-(JM3-Pad59)") (class "Default")
      (node (ref "JM3") (pin "59") (pinfunction "59_59") (pintype "passive+no_connect"))
    )
    (net (code "227") (name "unconnected-(U14-NC-Pad4)") (class "Default")
      (node (ref "U14") (pin "4") (pinfunction "NC_4") (pintype "passive+no_connect"))
    )
  )
)
